# phone.net
KiCad netlist of a schematic drawn in Altium Designer
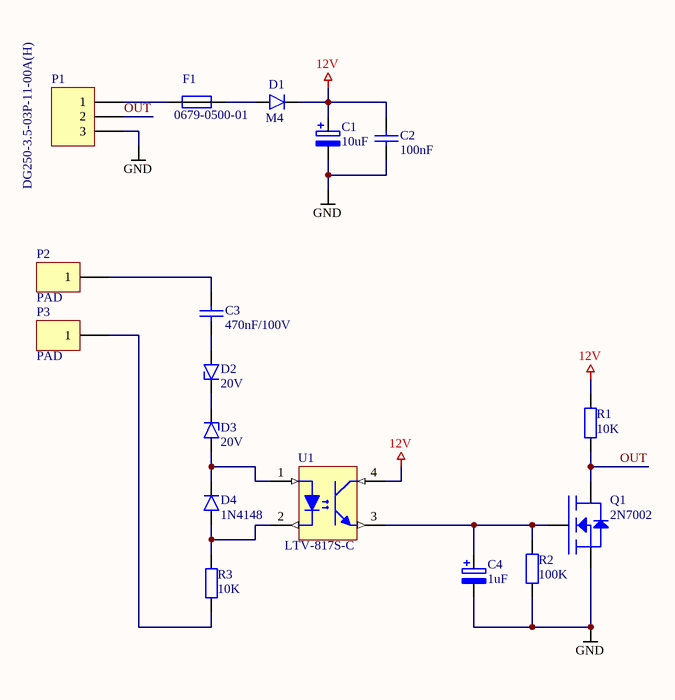
[diagram p0: phone.SchDoc]

(export (version "E")
  (design (tool "Eeschema 10.0.6"))
  (components
    (comp (ref "C1")
      (value "10uF")
      (footprint "TANC_B")
      (description "Capacitor Polarized")
      (libsource (lib "Library") (part "Cap_Pol"))
    )
    (comp (ref "C2")
      (value "100nF")
      (footprint "C0805")
      (description "Capacitor")
      (libsource (lib "Library") (part "Cap"))
    )
    (comp (ref "C3")
      (value "470nF/100V")
      (footprint "C1206")
      (description "Capacitor")
      (libsource (lib "Library") (part "Cap"))
    )
    (comp (ref "C4")
      (value "1uF")
      (footprint "TANC_A")
      (description "Capacitor Polarized")
      (libsource (lib "Library") (part "Cap_Pol"))
    )
    (comp (ref "D1") (value "M4") (footprint "SMA") (libsource (lib "Library") (part "Diode")))
    (comp (ref "D2") (value "20V") (footprint "SOD80C") (libsource (lib "Library") (part "Diode Zener")))
    (comp (ref "D3") (value "20V") (footprint "SOD80C") (libsource (lib "Library") (part "Diode Zener")))
    (comp (ref "D4") (value "1N4148") (footprint "SOD80C") (libsource (lib "Library") (part "Diode")))
    (comp (ref "F1")
      (value "0679-0500-01")
      (footprint "0679-0500-01")
      (description "Bezpiecznik: topikowy; szybki; ceramiczny; 500mA; 125VAC; 125VDC")
      (libsource (lib "Library") (part "0679-0500-01"))
    )
    (comp (ref "P1")
      (value "DG250-3.5-03P-11-00A(H)")
      (footprint "DG250-3.5-03P-11-00A(H)")
      (libsource (lib "Connectors") (part "DG250-3.5-03P-11-00A(H)"))
    )
    (comp (ref "P2") (value "PAD") (footprint "PAD") (libsource (lib "Connectors") (part "PAD")))
    (comp (ref "P3") (value "PAD") (footprint "PAD") (libsource (lib "Connectors") (part "PAD")))
    (comp (ref "Q1")
      (value "2N7002")
      (footprint "SOT23")
      (description "N-MOSFET")
      (libsource (lib "Library") (part "2N7002(GSD)"))
    )
    (comp (ref "R1")
      (value "10K")
      (footprint "R0805")
      (description "Resistor")
      (libsource (lib "Library") (part "Res"))
    )
    (comp (ref "R2")
      (value "100K")
      (footprint "R0805")
      (description "Resistor")
      (libsource (lib "Library") (part "Res"))
    )
    (comp (ref "R3")
      (value "10K")
      (footprint "R0805")
      (description "Resistor")
      (libsource (lib "") (part "Res_1"))
    )
    (comp (ref "U1")
      (value "LTV-817S-C")
      (footprint "LTV-817")
      (description "Transoptor; SMD; Kanały:1; Wyj: tranzystorowe; Uizol:5kV; Uce:35")
      (libsource (lib "Library") (part "LTV-817S-C"))
    )
  )
  (nets
    (net (code "1") (name "/OUT") (class "Default")
      (node (ref "P1") (pin "2") (pinfunction "2_2") (pintype "passive"))
      (node (ref "Q1") (pin "3") (pinfunction "D_3") (pintype "passive"))
      (node (ref "R1") (pin "1") (pinfunction "1_1") (pintype "passive"))
    )
    (net (code "2") (name "12V") (class "Default")
      (node (ref "C1") (pin "1") (pinfunction "1_1") (pintype "passive"))
      (node (ref "C2") (pin "1") (pinfunction "1_1") (pintype "passive"))
      (node (ref "D1") (pin "1") (pinfunction "1_1") (pintype "power_in"))
      (node (ref "R1") (pin "2") (pinfunction "2_2") (pintype "passive"))
      (node (ref "U1") (pin "4") (pinfunction "4_4") (pintype "input"))
    )
    (net (code "3") (name "GND") (class "Default")
      (node (ref "C1") (pin "2") (pinfunction "2_2") (pintype "passive"))
      (node (ref "C2") (pin "2") (pinfunction "2_2") (pintype "passive"))
      (node (ref "C4") (pin "2") (pinfunction "2_2") (pintype "passive"))
      (node (ref "P1") (pin "3") (pinfunction "3_3") (pintype "passive"))
      (node (ref "Q1") (pin "2") (pinfunction "S_2") (pintype "passive"))
      (node (ref "R2") (pin "1") (pinfunction "1_1") (pintype "passive"))
    )
    (net (code "4") (name "Net-(C3-Pad1)") (class "Default")
      (node (ref "C3") (pin "1") (pinfunction "1_1") (pintype "passive"))
      (node (ref "P2") (pin "1") (pinfunction "1_1") (pintype "passive"))
    )
    (net (code "5") (name "Net-(C3-Pad2)") (class "Default")
      (node (ref "C3") (pin "2") (pinfunction "2_2") (pintype "passive"))
      (node (ref "D2") (pin "2") (pinfunction "2_2") (pintype "power_in"))
    )
    (net (code "6") (name "Net-(D1-Pad2)") (class "Default")
      (node (ref "D1") (pin "2") (pinfunction "2_2") (pintype "power_in"))
      (node (ref "F1") (pin "2") (pinfunction "2_2") (pintype "passive"))
    )
    (net (code "7") (name "Net-(D2-Pad1)") (class "Default")
      (node (ref "D2") (pin "1") (pinfunction "1_1") (pintype "power_in"))
      (node (ref "D3") (pin "1") (pinfunction "1_1") (pintype "power_in"))
    )
    (net (code "8") (name "Net-(D3-Pad2)") (class "Default")
      (node (ref "D3") (pin "2") (pinfunction "2_2") (pintype "power_in"))
      (node (ref "D4") (pin "1") (pinfunction "1_1") (pintype "power_in"))
      (node (ref "U1") (pin "1") (pinfunction "1_1") (pintype "input"))
    )
    (net (code "9") (name "Net-(D4-Pad2)") (class "Default")
      (node (ref "D4") (pin "2") (pinfunction "2_2") (pintype "power_in"))
      (node (ref "R3") (pin "1") (pinfunction "1_1") (pintype "passive"))
      (node (ref "U1") (pin "2") (pinfunction "2_2") (pintype "output"))
    )
    (net (code "10") (name "Net-(F1-Pad1)") (class "Default")
      (node (ref "F1") (pin "1") (pinfunction "1_1") (pintype "passive"))
      (node (ref "P1") (pin "1") (pinfunction "1_1") (pintype "passive"))
    )
    (net (code "11") (name "Net-(P3-Pad1)") (class "Default")
      (node (ref "P3") (pin "1") (pinfunction "1_1") (pintype "passive"))
      (node (ref "R3") (pin "2") (pinfunction "2_2") (pintype "passive"))
    )
    (net (code "12") (name "Net-(Q1-G)") (class "Default")
      (node (ref "C4") (pin "1") (pinfunction "1_1") (pintype "passive"))
      (node (ref "Q1") (pin "1") (pinfunction "G_1") (pintype "passive"))
      (node (ref "R2") (pin "2") (pinfunction "2_2") (pintype "passive"))
      (node (ref "U1") (pin "3") (pinfunction "3_3") (pintype "output"))
    )
  )
)
